# 9.net
KiCad netlist of a schematic drawn in EasyEDA Pro
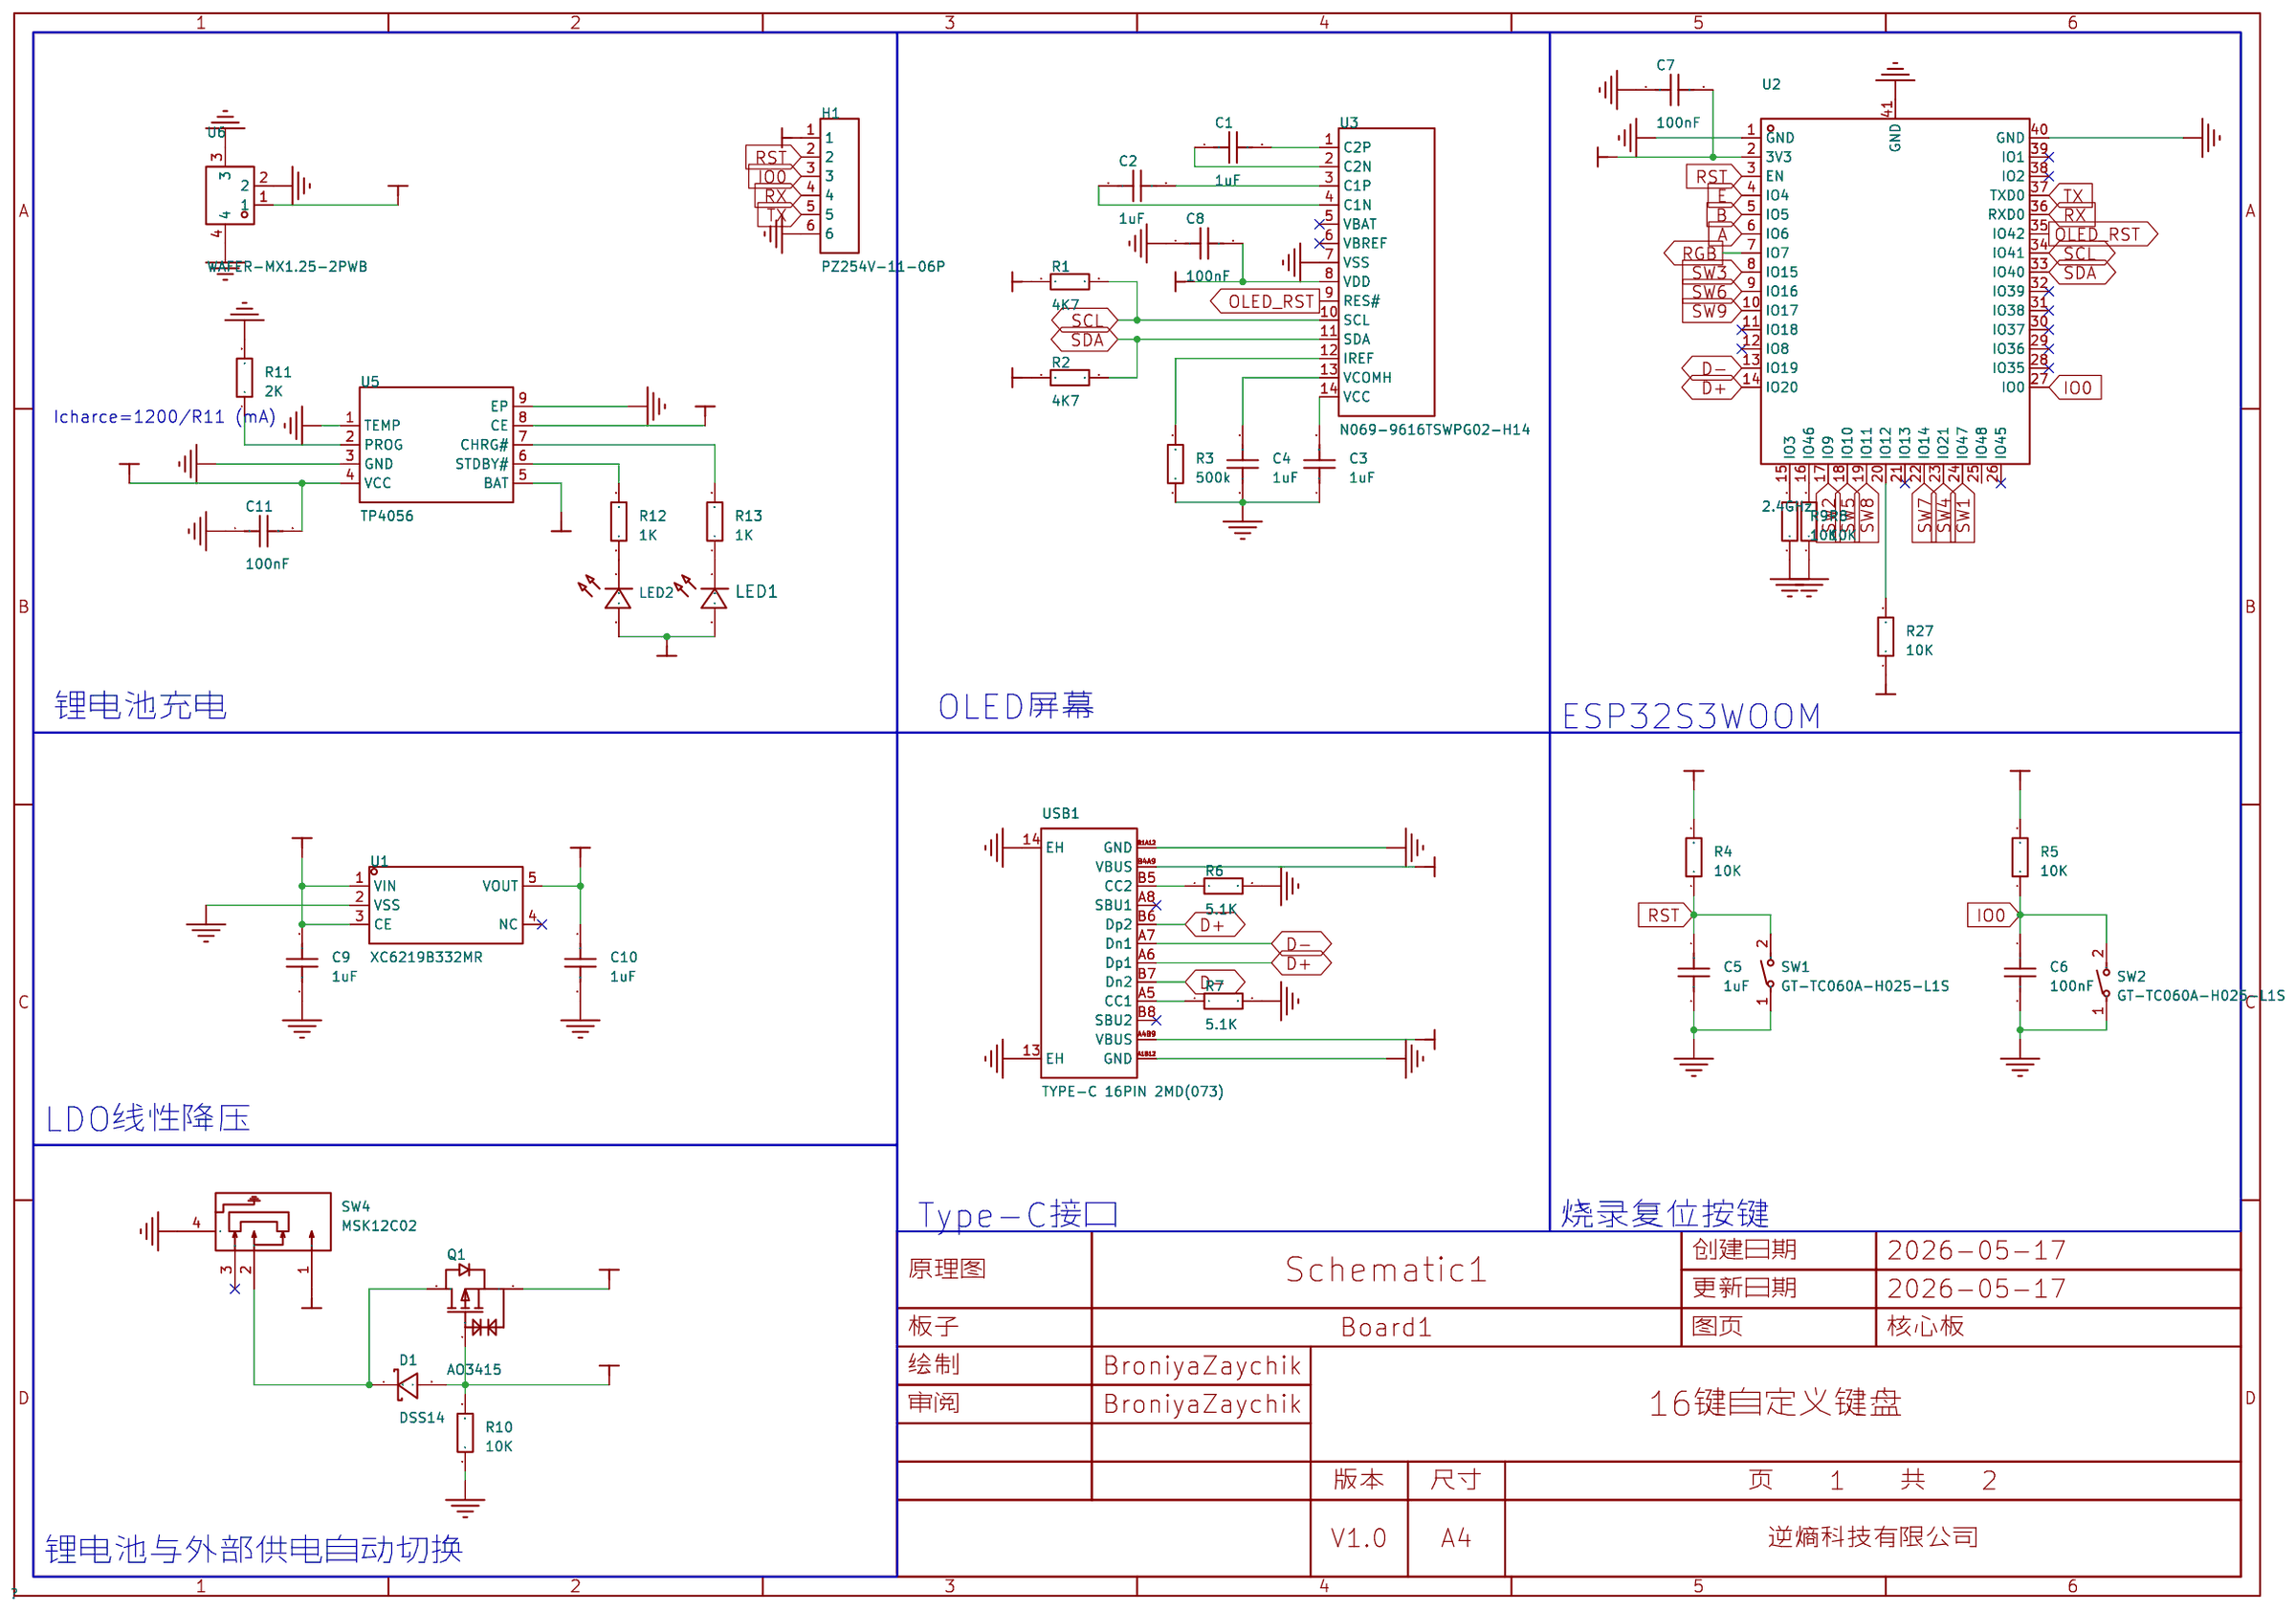
[diagram p0: 核心板]
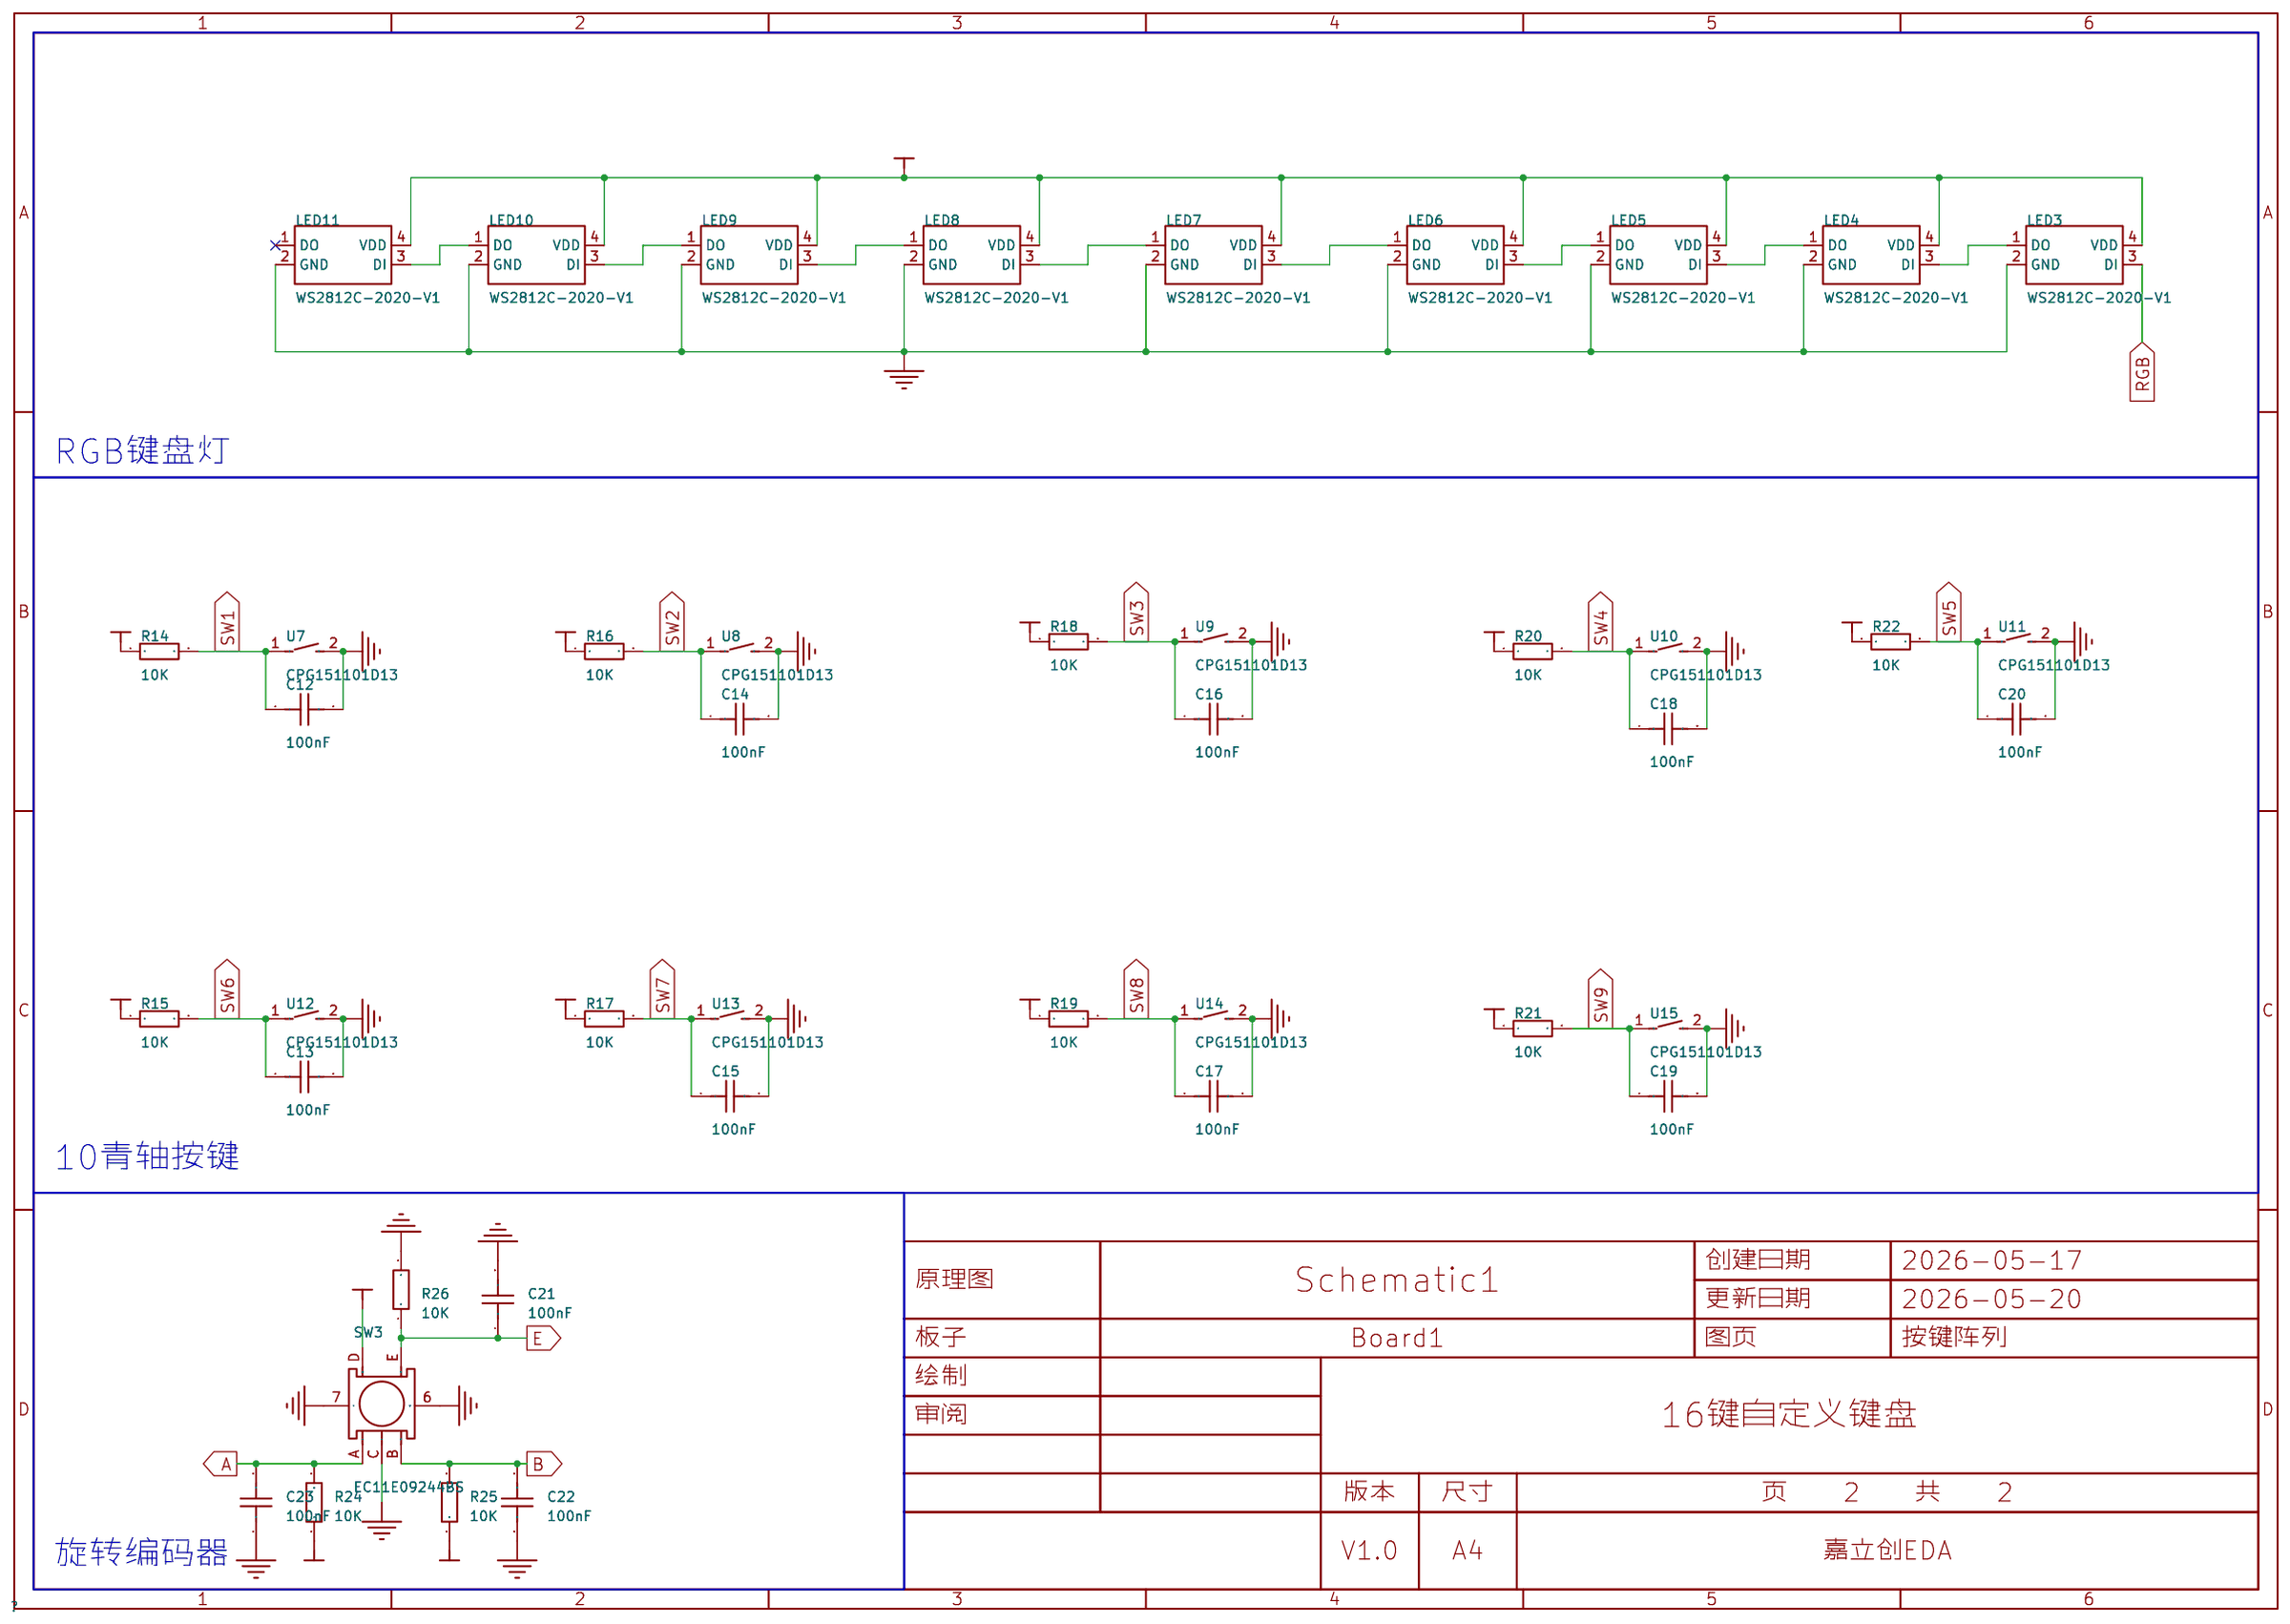
[diagram p1: 按键阵列]

(export (version "E")
  (design (tool "Eeschema 10.0.6"))
  (components
    (comp (ref "C1")
      (value "1uF")
      (footprint "easyedapro:C0603")
      (libsource (lib "easyedapro") (part "Capacitance"))
    )
    (comp (ref "C2")
      (value "1uF")
      (footprint "easyedapro:C0603")
      (libsource (lib "easyedapro") (part "Capacitance"))
    )
    (comp (ref "C3")
      (value "1uF")
      (footprint "easyedapro:C0603")
      (libsource (lib "easyedapro") (part "Capacitance"))
    )
    (comp (ref "C4")
      (value "1uF")
      (footprint "easyedapro:C0603")
      (libsource (lib "easyedapro") (part "Capacitance"))
    )
    (comp (ref "C5")
      (value "1uF")
      (footprint "easyedapro:C0603")
      (libsource (lib "easyedapro") (part "Capacitance"))
    )
    (comp (ref "C6")
      (value "100nF")
      (footprint "easyedapro:C0603")
      (libsource (lib "easyedapro") (part "Capacitance"))
    )
    (comp (ref "C7")
      (value "100nF")
      (footprint "easyedapro:C0603")
      (libsource (lib "easyedapro") (part "Capacitance"))
    )
    (comp (ref "C8")
      (value "100nF")
      (footprint "easyedapro:C0603")
      (libsource (lib "easyedapro") (part "Capacitance"))
    )
    (comp (ref "C9")
      (value "1uF")
      (footprint "easyedapro:C0603")
      (libsource (lib "easyedapro") (part "Capacitance"))
    )
    (comp (ref "C10")
      (value "1uF")
      (footprint "easyedapro:C0603")
      (libsource (lib "easyedapro") (part "Capacitance"))
    )
    (comp (ref "C11")
      (value "100nF")
      (footprint "easyedapro:C0603")
      (libsource (lib "easyedapro") (part "Capacitance"))
    )
    (comp (ref "D1")
      (value "DSS14")
      (footprint "easyedapro:SOD-123FL_L2.8-W1.8-LS3.7-RD")
      (fields (field (name "Manufacturer") "CJ(江苏长电/长晶)"))
      (libsource (lib "easyedapro") (part "DSS14_C2923923"))
    )
    (comp (ref "H1")
      (value "PZ254V-11-06P")
      (footprint "easyedapro:HDR-TH_6P-P2.54-V-M")
      (fields (field (name "Manufacturer") "XFCN(兴飞)"))
      (libsource (lib "easyedapro") (part "PZ254V-11-06P"))
    )
    (comp (ref "LED1")
      (value "~")
      (footprint "easyedapro:LED_0603")
      (libsource (lib "easyedapro") (part "LED_R"))
    )
    (comp (ref "LED2")
      (value "~")
      (footprint "easyedapro:LED_0603")
      (libsource (lib "easyedapro") (part "LED_G"))
    )
    (comp (ref "Q1")
      (value "AO3415")
      (footprint "easyedapro:SOT-23_L2.9-W1.3-P1.90-LS2.4-BR")
      (fields (field (name "Manufacturer") "GOODWORK(固得沃克)"))
      (libsource (lib "easyedapro") (part "AO3415_C2938370"))
    )
    (comp (ref "R1") (value "4K7") (footprint "easyedapro:R0603") (libsource (lib "easyedapro") (part "电阻")))
    (comp (ref "R2") (value "4K7") (footprint "easyedapro:R0603") (libsource (lib "easyedapro") (part "电阻")))
    (comp (ref "R3") (value "500k") (footprint "easyedapro:R0603") (libsource (lib "easyedapro") (part "电阻")))
    (comp (ref "R4") (value "10K") (footprint "easyedapro:R0603") (libsource (lib "easyedapro") (part "电阻")))
    (comp (ref "R5") (value "10K") (footprint "easyedapro:R0603") (libsource (lib "easyedapro") (part "电阻")))
    (comp (ref "R6") (value "5.1K") (footprint "easyedapro:R0603") (libsource (lib "easyedapro") (part "电阻")))
    (comp (ref "R7") (value "5.1K") (footprint "easyedapro:R0603") (libsource (lib "easyedapro") (part "电阻")))
    (comp (ref "R8") (value "10K") (footprint "easyedapro:R0603") (libsource (lib "easyedapro") (part "电阻")))
    (comp (ref "R9") (value "10K") (footprint "easyedapro:R0603") (libsource (lib "easyedapro") (part "电阻")))
    (comp (ref "R10") (value "10K") (footprint "easyedapro:R0603") (libsource (lib "easyedapro") (part "电阻")))
    (comp (ref "R11") (value "2K") (footprint "easyedapro:R0603") (libsource (lib "easyedapro") (part "电阻")))
    (comp (ref "R12") (value "1K") (footprint "easyedapro:R0603") (libsource (lib "easyedapro") (part "电阻")))
    (comp (ref "R13") (value "1K") (footprint "easyedapro:R0603") (libsource (lib "easyedapro") (part "电阻")))
    (comp (ref "R27") (value "10K") (footprint "easyedapro:R0603") (libsource (lib "easyedapro") (part "电阻")))
    (comp (ref "SW1")
      (value "GT-TC060A-H025-L1S")
      (footprint "easyedapro:SW-SMD_L6.1-W3.5-LS8.0")
      (fields (field (name "Manufacturer") "G-Switch(品赞)"))
      (libsource (lib "easyedapro") (part "GT-TC060A-H025-L1S"))
    )
    (comp (ref "SW2")
      (value "GT-TC060A-H025-L1S")
      (footprint "easyedapro:SW-SMD_L6.1-W3.5-LS8.0")
      (fields (field (name "Manufacturer") "G-Switch(品赞)"))
      (libsource (lib "easyedapro") (part "GT-TC060A-H025-L1S"))
    )
    (comp (ref "SW4")
      (value "MSK12C02")
      (footprint "easyedapro:SW-TH_MSK12C02")
      (fields (field (name "Manufacturer") "SHOU HAN(首韩)"))
      (libsource (lib "easyedapro") (part "MSK12C02"))
    )
    (comp (ref "U1")
      (value "XC6219B332MR")
      (footprint "easyedapro:SOT-23-5_L3.0-W1.7-P0.95-LS2.8-BR")
      (fields (field (name "Manufacturer") "UMW(友台半导体)"))
      (libsource (lib "easyedapro") (part "XC6219B332MR_C347386"))
    )
    (comp (ref "U2")
      (value "2.4GHz")
      (footprint "easyedapro:WIRELM-SMD_ESP32-S3-WROOM-1")
      (fields
        (field (name "Manufacturer Part") "ESP32-S3-WROOM-1-N8R8")
        (field (name "Manufacturer") "ESPRESSIF(乐鑫)")
      )
      (libsource (lib "easyedapro") (part "ESP32-S3-WROOM-1(N8R8)"))
    )
    (comp (ref "U3")
      (value "N069-9616TSWPG02-H14")
      (footprint "easyedapro:LCD-SMD_N069-9616TSWPG02-H14")
      (fields (field (name "Manufacturer") "Wisevision(新智景)"))
      (libsource (lib "easyedapro") (part "N069-9616TSWPG02-H14"))
    )
    (comp (ref "U5")
      (value "TP4056")
      (footprint "easyedapro:ESOP-8_L4.9-W3.9-P1.27-LS6.0-BL-EP")
      (fields (field (name "Manufacturer") "UMW(友台半导体)"))
      (libsource (lib "easyedapro") (part "TP4056_C725790"))
    )
    (comp (ref "U6")
      (value "WAFER-MX1.25-2PWB")
      (footprint "easyedapro:CONN-SMD_2P-P1.25_XUNPU_WAFER-MX1.25-2PWB")
      (fields (field (name "Manufacturer") "XUNPU(讯普)"))
      (libsource (lib "easyedapro") (part "WAFER-MX1.25-2PWB"))
    )
    (comp (ref "USB1")
      (value "TYPE-C 16PIN 2MD(073)")
      (footprint "easyedapro:USB-C-SMD_TYPE-C-16PIN-2MD-073")
      (fields (field (name "Manufacturer") "SHOU HAN(首韩)"))
      (libsource (lib "easyedapro") (part "TYPE-C 16PIN 2MD(073)"))
    )
    (comp (ref "C12")
      (value "100nF")
      (footprint "easyedapro:C0603")
      (libsource (lib "easyedapro") (part "Capacitance"))
    )
    (comp (ref "C13")
      (value "100nF")
      (footprint "easyedapro:C0603")
      (libsource (lib "easyedapro") (part "Capacitance"))
    )
    (comp (ref "C14")
      (value "100nF")
      (footprint "easyedapro:C0603")
      (libsource (lib "easyedapro") (part "Capacitance"))
    )
    (comp (ref "C15")
      (value "100nF")
      (footprint "easyedapro:C0603")
      (libsource (lib "easyedapro") (part "Capacitance"))
    )
    (comp (ref "C16")
      (value "100nF")
      (footprint "easyedapro:C0603")
      (libsource (lib "easyedapro") (part "Capacitance"))
    )
    (comp (ref "C17")
      (value "100nF")
      (footprint "easyedapro:C0603")
      (libsource (lib "easyedapro") (part "Capacitance"))
    )
    (comp (ref "C18")
      (value "100nF")
      (footprint "easyedapro:C0603")
      (libsource (lib "easyedapro") (part "Capacitance"))
    )
    (comp (ref "C19")
      (value "100nF")
      (footprint "easyedapro:C0603")
      (libsource (lib "easyedapro") (part "Capacitance"))
    )
    (comp (ref "C20")
      (value "100nF")
      (footprint "easyedapro:C0603")
      (libsource (lib "easyedapro") (part "Capacitance"))
    )
    (comp (ref "C21")
      (value "100nF")
      (footprint "easyedapro:C0603")
      (libsource (lib "easyedapro") (part "Capacitance"))
    )
    (comp (ref "C22")
      (value "100nF")
      (footprint "easyedapro:C0603")
      (libsource (lib "easyedapro") (part "Capacitance"))
    )
    (comp (ref "C23")
      (value "100nF")
      (footprint "easyedapro:C0603")
      (libsource (lib "easyedapro") (part "Capacitance"))
    )
    (comp (ref "LED3")
      (value "WS2812C-2020-V1")
      (footprint "easyedapro:LED-SMD_4P-L2.0-W2.0-TL_WS2812B-2020")
      (fields (field (name "Manufacturer") "worldsemi"))
      (libsource (lib "easyedapro") (part "WS2812C-2020-V1"))
    )
    (comp (ref "LED4")
      (value "WS2812C-2020-V1")
      (footprint "easyedapro:LED-SMD_4P-L2.0-W2.0-TL_WS2812B-2020")
      (fields (field (name "Manufacturer") "worldsemi"))
      (libsource (lib "easyedapro") (part "WS2812C-2020-V1"))
    )
    (comp (ref "LED5")
      (value "WS2812C-2020-V1")
      (footprint "easyedapro:LED-SMD_4P-L2.0-W2.0-TL_WS2812B-2020")
      (fields (field (name "Manufacturer") "worldsemi"))
      (libsource (lib "easyedapro") (part "WS2812C-2020-V1"))
    )
    (comp (ref "LED6")
      (value "WS2812C-2020-V1")
      (footprint "easyedapro:LED-SMD_4P-L2.0-W2.0-TL_WS2812B-2020")
      (fields (field (name "Manufacturer") "worldsemi"))
      (libsource (lib "easyedapro") (part "WS2812C-2020-V1"))
    )
    (comp (ref "LED7")
      (value "WS2812C-2020-V1")
      (footprint "easyedapro:LED-SMD_4P-L2.0-W2.0-TL_WS2812B-2020")
      (fields (field (name "Manufacturer") "worldsemi"))
      (libsource (lib "easyedapro") (part "WS2812C-2020-V1"))
    )
    (comp (ref "LED8")
      (value "WS2812C-2020-V1")
      (footprint "easyedapro:LED-SMD_4P-L2.0-W2.0-TL_WS2812B-2020")
      (fields (field (name "Manufacturer") "worldsemi"))
      (libsource (lib "easyedapro") (part "WS2812C-2020-V1"))
    )
    (comp (ref "LED9")
      (value "WS2812C-2020-V1")
      (footprint "easyedapro:LED-SMD_4P-L2.0-W2.0-TL_WS2812B-2020")
      (fields (field (name "Manufacturer") "worldsemi"))
      (libsource (lib "easyedapro") (part "WS2812C-2020-V1"))
    )
    (comp (ref "LED10")
      (value "WS2812C-2020-V1")
      (footprint "easyedapro:LED-SMD_4P-L2.0-W2.0-TL_WS2812B-2020")
      (fields (field (name "Manufacturer") "worldsemi"))
      (libsource (lib "easyedapro") (part "WS2812C-2020-V1"))
    )
    (comp (ref "LED11")
      (value "WS2812C-2020-V1")
      (footprint "easyedapro:LED-SMD_4P-L2.0-W2.0-TL_WS2812B-2020")
      (fields (field (name "Manufacturer") "worldsemi"))
      (libsource (lib "easyedapro") (part "WS2812C-2020-V1"))
    )
    (comp (ref "R14") (value "10K") (footprint "easyedapro:R0603") (libsource (lib "easyedapro") (part "电阻")))
    (comp (ref "R15") (value "10K") (footprint "easyedapro:R0603") (libsource (lib "easyedapro") (part "电阻")))
    (comp (ref "R16") (value "10K") (footprint "easyedapro:R0603") (libsource (lib "easyedapro") (part "电阻")))
    (comp (ref "R17") (value "10K") (footprint "easyedapro:R0603") (libsource (lib "easyedapro") (part "电阻")))
    (comp (ref "R18") (value "10K") (footprint "easyedapro:R0603") (libsource (lib "easyedapro") (part "电阻")))
    (comp (ref "R19") (value "10K") (footprint "easyedapro:R0603") (libsource (lib "easyedapro") (part "电阻")))
    (comp (ref "R20") (value "10K") (footprint "easyedapro:R0603") (libsource (lib "easyedapro") (part "电阻")))
    (comp (ref "R21") (value "10K") (footprint "easyedapro:R0603") (libsource (lib "easyedapro") (part "电阻")))
    (comp (ref "R22") (value "10K") (footprint "easyedapro:R0603") (libsource (lib "easyedapro") (part "电阻")))
    (comp (ref "R24") (value "10K") (footprint "easyedapro:R0603") (libsource (lib "easyedapro") (part "电阻")))
    (comp (ref "R25") (value "10K") (footprint "easyedapro:R0603") (libsource (lib "easyedapro") (part "电阻")))
    (comp (ref "R26") (value "10K") (footprint "easyedapro:R0603") (libsource (lib "easyedapro") (part "电阻")))
    (comp (ref "SW3")
      (value "EC11E09244BS")
      (footprint "easyedapro:SW-TH_EC11XXXXXXXX")
      (fields (field (name "Manufacturer") "ALPSALPINE(阿尔卑斯阿尔派)"))
      (libsource (lib "easyedapro") (part "EC11E09244BS"))
    )
    (comp (ref "U7")
      (value "CPG151101D13")
      (footprint "easyedapro:KEY-TH_CPG151101D21X")
      (fields (field (name "Manufacturer") "HanElectricity(瀚源)"))
      (libsource (lib "easyedapro") (part "CPG151101D13"))
    )
    (comp (ref "U8")
      (value "CPG151101D13")
      (footprint "easyedapro:KEY-TH_CPG151101D21X")
      (fields (field (name "Manufacturer") "HanElectricity(瀚源)"))
      (libsource (lib "easyedapro") (part "CPG151101D13"))
    )
    (comp (ref "U9")
      (value "CPG151101D13")
      (footprint "easyedapro:KEY-TH_CPG151101D21X")
      (fields (field (name "Manufacturer") "HanElectricity(瀚源)"))
      (libsource (lib "easyedapro") (part "CPG151101D13"))
    )
    (comp (ref "U10")
      (value "CPG151101D13")
      (footprint "easyedapro:KEY-TH_CPG151101D21X")
      (fields (field (name "Manufacturer") "HanElectricity(瀚源)"))
      (libsource (lib "easyedapro") (part "CPG151101D13"))
    )
    (comp (ref "U11")
      (value "CPG151101D13")
      (footprint "easyedapro:KEY-TH_CPG151101D21X")
      (fields (field (name "Manufacturer") "HanElectricity(瀚源)"))
      (libsource (lib "easyedapro") (part "CPG151101D13"))
    )
    (comp (ref "U12")
      (value "CPG151101D13")
      (footprint "easyedapro:KEY-TH_CPG151101D21X")
      (fields (field (name "Manufacturer") "HanElectricity(瀚源)"))
      (libsource (lib "easyedapro") (part "CPG151101D13"))
    )
    (comp (ref "U13")
      (value "CPG151101D13")
      (footprint "easyedapro:KEY-TH_CPG151101D21X")
      (fields (field (name "Manufacturer") "HanElectricity(瀚源)"))
      (libsource (lib "easyedapro") (part "CPG151101D13"))
    )
    (comp (ref "U14")
      (value "CPG151101D13")
      (footprint "easyedapro:KEY-TH_CPG151101D21X")
      (fields (field (name "Manufacturer") "HanElectricity(瀚源)"))
      (libsource (lib "easyedapro") (part "CPG151101D13"))
    )
    (comp (ref "U15")
      (value "CPG151101D13")
      (footprint "easyedapro:KEY-TH_CPG151101D21X")
      (fields (field (name "Manufacturer") "HanElectricity(瀚源)"))
      (libsource (lib "easyedapro") (part "CPG151101D13"))
    )
  )
  (nets
    (net (code "1") (name "+5V") (class "Default")
      (node (ref "C11") (pin "2") (pinfunction "2_2") (pintype "input"))
      (node (ref "D1") (pin "2") (pinfunction "A_2") (pintype "unspecified"))
      (node (ref "LED1") (pin "2") (pinfunction "A_2") (pintype "input"))
      (node (ref "LED2") (pin "2") (pinfunction "A_2") (pintype "input"))
      (node (ref "Q1") (pin "1") (pinfunction "G_1") (pintype "unspecified"))
      (node (ref "R10") (pin "2") (pinfunction "2_2") (pintype "input"))
      (node (ref "R27") (pin "1") (pinfunction "1_1") (pintype "input"))
      (node (ref "U5") (pin "4") (pinfunction "VCC_4") (pintype "unspecified"))
      (node (ref "U5") (pin "8") (pinfunction "CE_8") (pintype "unspecified"))
      (node (ref "USB1") (pin "A4B9") (pinfunction "VBUS_A4B9") (pintype "unspecified"))
      (node (ref "USB1") (pin "B4A9") (pinfunction "VBUS_B4A9") (pintype "unspecified"))
    )
    (net (code "2") (name "3V3") (class "Default")
      (node (ref "C10") (pin "1") (pinfunction "1_1") (pintype "input"))
      (node (ref "C7") (pin "2") (pinfunction "2_2") (pintype "input"))
      (node (ref "C8") (pin "2") (pinfunction "2_2") (pintype "input"))
      (node (ref "H1") (pin "1") (pinfunction "1_1") (pintype "unspecified"))
      (node (ref "R1") (pin "1") (pinfunction "1_1") (pintype "input"))
      (node (ref "R14") (pin "1") (pinfunction "1_1") (pintype "input"))
      (node (ref "R15") (pin "1") (pinfunction "1_1") (pintype "input"))
      (node (ref "R16") (pin "1") (pinfunction "1_1") (pintype "input"))
      (node (ref "R17") (pin "1") (pinfunction "1_1") (pintype "input"))
      (node (ref "R18") (pin "1") (pinfunction "1_1") (pintype "input"))
      (node (ref "R19") (pin "1") (pinfunction "1_1") (pintype "input"))
      (node (ref "R2") (pin "1") (pinfunction "1_1") (pintype "input"))
      (node (ref "R20") (pin "1") (pinfunction "1_1") (pintype "input"))
      (node (ref "R21") (pin "1") (pinfunction "1_1") (pintype "input"))
      (node (ref "R22") (pin "1") (pinfunction "1_1") (pintype "input"))
      (node (ref "R24") (pin "1") (pinfunction "1_1") (pintype "input"))
      (node (ref "R25") (pin "1") (pinfunction "1_1") (pintype "input"))
      (node (ref "R4") (pin "2") (pinfunction "2_2") (pintype "input"))
      (node (ref "R5") (pin "2") (pinfunction "2_2") (pintype "input"))
      (node (ref "SW3") (pin "D") (pinfunction "D_D") (pintype "unspecified"))
      (node (ref "U1") (pin "5") (pinfunction "VOUT_5") (pintype "unspecified"))
      (node (ref "U2") (pin "2") (pinfunction "3V3_2") (pintype "unspecified"))
      (node (ref "U3") (pin "8") (pinfunction "VDD_8") (pintype "unspecified"))
    )
    (net (code "3") (name "A") (class "Default")
      (node (ref "C23") (pin "2") (pinfunction "2_2") (pintype "input"))
      (node (ref "R24") (pin "2") (pinfunction "2_2") (pintype "input"))
      (node (ref "SW3") (pin "A") (pinfunction "A_A") (pintype "unspecified"))
      (node (ref "U2") (pin "6") (pinfunction "IO6_6") (pintype "unspecified"))
    )
    (net (code "4") (name "B") (class "Default")
      (node (ref "C22") (pin "2") (pinfunction "2_2") (pintype "input"))
      (node (ref "R25") (pin "2") (pinfunction "2_2") (pintype "input"))
      (node (ref "SW3") (pin "B") (pinfunction "B_B") (pintype "unspecified"))
      (node (ref "U2") (pin "5") (pinfunction "IO5_5") (pintype "unspecified"))
    )
    (net (code "5") (name "D+") (class "Default")
      (node (ref "U2") (pin "14") (pinfunction "IO20_14") (pintype "unspecified"))
      (node (ref "USB1") (pin "A6") (pinfunction "Dp1_A6") (pintype "unspecified"))
      (node (ref "USB1") (pin "B6") (pinfunction "Dp2_B6") (pintype "unspecified"))
    )
    (net (code "6") (name "D-") (class "Default")
      (node (ref "U2") (pin "13") (pinfunction "IO19_13") (pintype "unspecified"))
      (node (ref "USB1") (pin "A7") (pinfunction "Dn1_A7") (pintype "unspecified"))
      (node (ref "USB1") (pin "B7") (pinfunction "Dn2_B7") (pintype "unspecified"))
    )
    (net (code "7") (name "E") (class "Default")
      (node (ref "C21") (pin "1") (pinfunction "1_1") (pintype "input"))
      (node (ref "R26") (pin "1") (pinfunction "1_1") (pintype "input"))
      (node (ref "SW3") (pin "E") (pinfunction "E_E") (pintype "unspecified"))
      (node (ref "U2") (pin "4") (pinfunction "IO4_4") (pintype "unspecified"))
    )
    (net (code "8") (name "GND") (class "Default")
      (node (ref "C10") (pin "2") (pinfunction "2_2") (pintype "input"))
      (node (ref "C11") (pin "1") (pinfunction "1_1") (pintype "input"))
      (node (ref "C12") (pin "2") (pinfunction "2_2") (pintype "input"))
      (node (ref "C13") (pin "2") (pinfunction "2_2") (pintype "input"))
      (node (ref "C14") (pin "2") (pinfunction "2_2") (pintype "input"))
      (node (ref "C15") (pin "2") (pinfunction "2_2") (pintype "input"))
      (node (ref "C16") (pin "2") (pinfunction "2_2") (pintype "input"))
      (node (ref "C17") (pin "2") (pinfunction "2_2") (pintype "input"))
      (node (ref "C18") (pin "2") (pinfunction "2_2") (pintype "input"))
      (node (ref "C19") (pin "2") (pinfunction "2_2") (pintype "input"))
      (node (ref "C20") (pin "2") (pinfunction "2_2") (pintype "input"))
      (node (ref "C21") (pin "2") (pinfunction "2_2") (pintype "input"))
      (node (ref "C22") (pin "1") (pinfunction "1_1") (pintype "input"))
      (node (ref "C23") (pin "1") (pinfunction "1_1") (pintype "input"))
      (node (ref "C3") (pin "1") (pinfunction "1_1") (pintype "input"))
      (node (ref "C4") (pin "1") (pinfunction "1_1") (pintype "input"))
      (node (ref "C5") (pin "2") (pinfunction "2_2") (pintype "input"))
      (node (ref "C6") (pin "2") (pinfunction "2_2") (pintype "input"))
      (node (ref "C7") (pin "1") (pinfunction "1_1") (pintype "input"))
      (node (ref "C8") (pin "1") (pinfunction "1_1") (pintype "input"))
      (node (ref "C9") (pin "1") (pinfunction "1_1") (pintype "input"))
      (node (ref "H1") (pin "6") (pinfunction "6_6") (pintype "unspecified"))
      (node (ref "LED10") (pin "2") (pinfunction "GND_2") (pintype "unspecified"))
      (node (ref "LED11") (pin "2") (pinfunction "GND_2") (pintype "unspecified"))
      (node (ref "LED3") (pin "2") (pinfunction "GND_2") (pintype "unspecified"))
      (node (ref "LED4") (pin "2") (pinfunction "GND_2") (pintype "unspecified"))
      (node (ref "LED5") (pin "2") (pinfunction "GND_2") (pintype "unspecified"))
      (node (ref "LED6") (pin "2") (pinfunction "GND_2") (pintype "unspecified"))
      (node (ref "LED7") (pin "2") (pinfunction "GND_2") (pintype "unspecified"))
      (node (ref "LED8") (pin "2") (pinfunction "GND_2") (pintype "unspecified"))
      (node (ref "LED9") (pin "2") (pinfunction "GND_2") (pintype "unspecified"))
      (node (ref "R10") (pin "1") (pinfunction "1_1") (pintype "input"))
      (node (ref "R11") (pin "2") (pinfunction "2_2") (pintype "input"))
      (node (ref "R26") (pin "2") (pinfunction "2_2") (pintype "input"))
      (node (ref "R3") (pin "1") (pinfunction "1_1") (pintype "input"))
      (node (ref "R6") (pin "2") (pinfunction "2_2") (pintype "input"))
      (node (ref "R7") (pin "2") (pinfunction "2_2") (pintype "input"))
      (node (ref "R8") (pin "1") (pinfunction "1_1") (pintype "input"))
      (node (ref "R9") (pin "1") (pinfunction "1_1") (pintype "input"))
      (node (ref "SW1") (pin "1") (pinfunction "1_1") (pintype "unspecified"))
      (node (ref "SW2") (pin "1") (pinfunction "1_1") (pintype "unspecified"))
      (node (ref "SW3") (pin "6") (pinfunction "6_6") (pintype "unspecified"))
      (node (ref "SW3") (pin "7") (pinfunction "7_7") (pintype "unspecified"))
      (node (ref "SW3") (pin "C") (pinfunction "C_C") (pintype "unspecified"))
      (node (ref "SW4") (pin "4") (pinfunction "4_4") (pintype "unspecified"))
      (node (ref "U1") (pin "2") (pinfunction "VSS_2") (pintype "unspecified"))
      (node (ref "U10") (pin "2") (pinfunction "2_2") (pintype "unspecified"))
      (node (ref "U11") (pin "2") (pinfunction "2_2") (pintype "unspecified"))
      (node (ref "U12") (pin "2") (pinfunction "2_2") (pintype "unspecified"))
      (node (ref "U13") (pin "2") (pinfunction "2_2") (pintype "unspecified"))
      (node (ref "U14") (pin "2") (pinfunction "2_2") (pintype "unspecified"))
      (node (ref "U15") (pin "2") (pinfunction "2_2") (pintype "unspecified"))
      (node (ref "U2") (pin "1") (pinfunction "GND_1") (pintype "unspecified"))
      (node (ref "U2") (pin "40") (pinfunction "GND_40") (pintype "unspecified"))
      (node (ref "U2") (pin "41") (pinfunction "GND_41") (pintype "unspecified"))
      (node (ref "U3") (pin "7") (pinfunction "VSS_7") (pintype "unspecified"))
      (node (ref "U5") (pin "1") (pinfunction "TEMP_1") (pintype "unspecified"))
      (node (ref "U5") (pin "3") (pinfunction "GND_3") (pintype "unspecified"))
      (node (ref "U5") (pin "9") (pinfunction "EP_9") (pintype "unspecified"))
      (node (ref "U6") (pin "2") (pinfunction "2_2") (pintype "unspecified"))
      (node (ref "U6") (pin "3") (pinfunction "3_3") (pintype "unspecified"))
      (node (ref "U6") (pin "4") (pinfunction "4_4") (pintype "unspecified"))
      (node (ref "U7") (pin "2") (pinfunction "2_2") (pintype "unspecified"))
      (node (ref "U8") (pin "2") (pinfunction "2_2") (pintype "unspecified"))
      (node (ref "U9") (pin "2") (pinfunction "2_2") (pintype "unspecified"))
      (node (ref "USB1") (pin "13") (pinfunction "EH_13") (pintype "unspecified"))
      (node (ref "USB1") (pin "14") (pinfunction "EH_14") (pintype "unspecified"))
      (node (ref "USB1") (pin "A1B12") (pinfunction "GND_A1B12") (pintype "unspecified"))
      (node (ref "USB1") (pin "B1A12") (pinfunction "GND_B1A12") (pintype "unspecified"))
    )
    (net (code "9") (name "IO0") (class "Default")
      (node (ref "C6") (pin "1") (pinfunction "1_1") (pintype "input"))
      (node (ref "H1") (pin "3") (pinfunction "3_3") (pintype "unspecified"))
      (node (ref "R5") (pin "1") (pinfunction "1_1") (pintype "input"))
      (node (ref "SW2") (pin "2") (pinfunction "2_2") (pintype "unspecified"))
      (node (ref "U2") (pin "27") (pinfunction "IO0_27") (pintype "unspecified"))
    )
    (net (code "10") (name "Net-(D1-C)") (class "Default")
      (node (ref "D1") (pin "1") (pinfunction "C_1") (pintype "unspecified"))
      (node (ref "Q1") (pin "3") (pinfunction "D_3") (pintype "unspecified"))
      (node (ref "SW4") (pin "2") (pinfunction "2_2") (pintype "unspecified"))
    )
    (net (code "11") (name "Net-(LED1-C)") (class "Default")
      (node (ref "LED1") (pin "1") (pinfunction "C_1") (pintype "input"))
      (node (ref "R13") (pin "1") (pinfunction "1_1") (pintype "input"))
    )
    (net (code "12") (name "Net-(LED2-C)") (class "Default")
      (node (ref "LED2") (pin "1") (pinfunction "C_1") (pintype "input"))
      (node (ref "R12") (pin "1") (pinfunction "1_1") (pintype "input"))
    )
    (net (code "13") (name "Net-(LED3-DO)") (class "Default")
      (node (ref "LED3") (pin "1") (pinfunction "DO_1") (pintype "unspecified"))
      (node (ref "LED4") (pin "3") (pinfunction "DI_3") (pintype "unspecified"))
    )
    (net (code "14") (name "Net-(LED4-DO)") (class "Default")
      (node (ref "LED4") (pin "1") (pinfunction "DO_1") (pintype "unspecified"))
      (node (ref "LED5") (pin "3") (pinfunction "DI_3") (pintype "unspecified"))
    )
    (net (code "15") (name "Net-(LED5-DO)") (class "Default")
      (node (ref "LED5") (pin "1") (pinfunction "DO_1") (pintype "unspecified"))
      (node (ref "LED6") (pin "3") (pinfunction "DI_3") (pintype "unspecified"))
    )
    (net (code "16") (name "Net-(LED6-DO)") (class "Default")
      (node (ref "LED6") (pin "1") (pinfunction "DO_1") (pintype "unspecified"))
      (node (ref "LED7") (pin "3") (pinfunction "DI_3") (pintype "unspecified"))
    )
    (net (code "17") (name "Net-(LED7-DO)") (class "Default")
      (node (ref "LED7") (pin "1") (pinfunction "DO_1") (pintype "unspecified"))
      (node (ref "LED8") (pin "3") (pinfunction "DI_3") (pintype "unspecified"))
    )
    (net (code "18") (name "Net-(LED8-DO)") (class "Default")
      (node (ref "LED8") (pin "1") (pinfunction "DO_1") (pintype "unspecified"))
      (node (ref "LED9") (pin "3") (pinfunction "DI_3") (pintype "unspecified"))
    )
    (net (code "19") (name "Net-(LED10-DI)") (class "Default")
      (node (ref "LED10") (pin "3") (pinfunction "DI_3") (pintype "unspecified"))
      (node (ref "LED9") (pin "1") (pinfunction "DO_1") (pintype "unspecified"))
    )
    (net (code "20") (name "Net-(LED10-DO)") (class "Default")
      (node (ref "LED10") (pin "1") (pinfunction "DO_1") (pintype "unspecified"))
      (node (ref "LED11") (pin "3") (pinfunction "DI_3") (pintype "unspecified"))
    )
    (net (code "21") (name "Net-(U2-IO3)") (class "Default")
      (node (ref "R9") (pin "2") (pinfunction "2_2") (pintype "input"))
      (node (ref "U2") (pin "15") (pinfunction "IO3_15") (pintype "unspecified"))
    )
    (net (code "22") (name "Net-(U2-IO12)") (class "Default")
      (node (ref "R27") (pin "2") (pinfunction "2_2") (pintype "input"))
      (node (ref "U2") (pin "20") (pinfunction "IO12_20") (pintype "unspecified"))
    )
    (net (code "23") (name "Net-(U2-IO46)") (class "Default")
      (node (ref "R8") (pin "2") (pinfunction "2_2") (pintype "input"))
      (node (ref "U2") (pin "16") (pinfunction "IO46_16") (pintype "unspecified"))
    )
    (net (code "24") (name "Net-(U3-C1N)") (class "Default")
      (node (ref "C2") (pin "1") (pinfunction "1_1") (pintype "input"))
      (node (ref "U3") (pin "4") (pinfunction "C1N_4") (pintype "unspecified"))
    )
    (net (code "25") (name "Net-(U3-C1P)") (class "Default")
      (node (ref "C2") (pin "2") (pinfunction "2_2") (pintype "input"))
      (node (ref "U3") (pin "3") (pinfunction "C1P_3") (pintype "unspecified"))
    )
    (net (code "26") (name "Net-(U3-C2N)") (class "Default")
      (node (ref "C1") (pin "1") (pinfunction "1_1") (pintype "input"))
      (node (ref "U3") (pin "2") (pinfunction "C2N_2") (pintype "unspecified"))
    )
    (net (code "27") (name "Net-(U3-C2P)") (class "Default")
      (node (ref "C1") (pin "2") (pinfunction "2_2") (pintype "input"))
      (node (ref "U3") (pin "1") (pinfunction "C2P_1") (pintype "unspecified"))
    )
    (net (code "28") (name "Net-(U3-IREF)") (class "Default")
      (node (ref "R3") (pin "2") (pinfunction "2_2") (pintype "input"))
      (node (ref "U3") (pin "12") (pinfunction "IREF_12") (pintype "unspecified"))
    )
    (net (code "29") (name "Net-(U3-VCC)") (class "Default")
      (node (ref "C3") (pin "2") (pinfunction "2_2") (pintype "input"))
      (node (ref "U3") (pin "14") (pinfunction "VCC_14") (pintype "unspecified"))
    )
    (net (code "30") (name "Net-(U3-VCOMH)") (class "Default")
      (node (ref "C4") (pin "2") (pinfunction "2_2") (pintype "input"))
      (node (ref "U3") (pin "13") (pinfunction "VCOMH_13") (pintype "unspecified"))
    )
    (net (code "31") (name "Net-(U5-CHRG#)") (class "Default")
      (node (ref "R13") (pin "2") (pinfunction "2_2") (pintype "input"))
      (node (ref "U5") (pin "7") (pinfunction "CHRG#_7") (pintype "unspecified"))
    )
    (net (code "32") (name "Net-(U5-PROG)") (class "Default")
      (node (ref "R11") (pin "1") (pinfunction "1_1") (pintype "input"))
      (node (ref "U5") (pin "2") (pinfunction "PROG_2") (pintype "unspecified"))
    )
    (net (code "33") (name "Net-(U5-STDBY#)") (class "Default")
      (node (ref "R12") (pin "2") (pinfunction "2_2") (pintype "input"))
      (node (ref "U5") (pin "6") (pinfunction "STDBY#_6") (pintype "unspecified"))
    )
    (net (code "34") (name "Net-(USB1-CC1)") (class "Default")
      (node (ref "R7") (pin "1") (pinfunction "1_1") (pintype "input"))
      (node (ref "USB1") (pin "A5") (pinfunction "CC1_A5") (pintype "unspecified"))
    )
    (net (code "35") (name "Net-(USB1-CC2)") (class "Default")
      (node (ref "R6") (pin "1") (pinfunction "1_1") (pintype "input"))
      (node (ref "USB1") (pin "B5") (pinfunction "CC2_B5") (pintype "unspecified"))
    )
    (net (code "36") (name "OLED_RST") (class "Default")
      (node (ref "U2") (pin "35") (pinfunction "IO42_35") (pintype "unspecified"))
      (node (ref "U3") (pin "9") (pinfunction "RES#_9") (pintype "unspecified"))
    )
    (net (code "37") (name "RGB") (class "Default")
      (node (ref "LED3") (pin "3") (pinfunction "DI_3") (pintype "unspecified"))
      (node (ref "U2") (pin "7") (pinfunction "IO7_7") (pintype "unspecified"))
    )
    (net (code "38") (name "RST") (class "Default")
      (node (ref "C5") (pin "1") (pinfunction "1_1") (pintype "input"))
      (node (ref "H1") (pin "2") (pinfunction "2_2") (pintype "unspecified"))
      (node (ref "R4") (pin "1") (pinfunction "1_1") (pintype "input"))
      (node (ref "SW1") (pin "2") (pinfunction "2_2") (pintype "unspecified"))
      (node (ref "U2") (pin "3") (pinfunction "EN_3") (pintype "unspecified"))
    )
    (net (code "39") (name "RX") (class "Default")
      (node (ref "H1") (pin "4") (pinfunction "4_4") (pintype "unspecified"))
      (node (ref "U2") (pin "36") (pinfunction "RXD0_36") (pintype "unspecified"))
    )
    (net (code "40") (name "SCL") (class "Default")
      (node (ref "R1") (pin "2") (pinfunction "2_2") (pintype "input"))
      (node (ref "U2") (pin "34") (pinfunction "IO41_34") (pintype "unspecified"))
      (node (ref "U3") (pin "10") (pinfunction "SCL_10") (pintype "unspecified"))
    )
    (net (code "41") (name "SDA") (class "Default")
      (node (ref "R2") (pin "2") (pinfunction "2_2") (pintype "input"))
      (node (ref "U2") (pin "33") (pinfunction "IO40_33") (pintype "unspecified"))
      (node (ref "U3") (pin "11") (pinfunction "SDA_11") (pintype "unspecified"))
    )
    (net (code "42") (name "SW1") (class "Default")
      (node (ref "C12") (pin "1") (pinfunction "1_1") (pintype "input"))
      (node (ref "R14") (pin "2") (pinfunction "2_2") (pintype "input"))
      (node (ref "U2") (pin "24") (pinfunction "IO47_24") (pintype "unspecified"))
      (node (ref "U7") (pin "1") (pinfunction "1_1") (pintype "unspecified"))
    )
    (net (code "43") (name "SW2") (class "Default")
      (node (ref "C14") (pin "1") (pinfunction "1_1") (pintype "input"))
      (node (ref "R16") (pin "2") (pinfunction "2_2") (pintype "input"))
      (node (ref "U2") (pin "17") (pinfunction "IO9_17") (pintype "unspecified"))
      (node (ref "U8") (pin "1") (pinfunction "1_1") (pintype "unspecified"))
    )
    (net (code "44") (name "SW3") (class "Default")
      (node (ref "C16") (pin "1") (pinfunction "1_1") (pintype "input"))
      (node (ref "R18") (pin "2") (pinfunction "2_2") (pintype "input"))
      (node (ref "U2") (pin "8") (pinfunction "IO15_8") (pintype "unspecified"))
      (node (ref "U9") (pin "1") (pinfunction "1_1") (pintype "unspecified"))
    )
    (net (code "45") (name "SW4") (class "Default")
      (node (ref "C18") (pin "1") (pinfunction "1_1") (pintype "input"))
      (node (ref "R20") (pin "2") (pinfunction "2_2") (pintype "input"))
      (node (ref "U10") (pin "1") (pinfunction "1_1") (pintype "unspecified"))
      (node (ref "U2") (pin "23") (pinfunction "IO21_23") (pintype "unspecified"))
    )
    (net (code "46") (name "SW5") (class "Default")
      (node (ref "C20") (pin "1") (pinfunction "1_1") (pintype "input"))
      (node (ref "R22") (pin "2") (pinfunction "2_2") (pintype "input"))
      (node (ref "U11") (pin "1") (pinfunction "1_1") (pintype "unspecified"))
      (node (ref "U2") (pin "18") (pinfunction "IO10_18") (pintype "unspecified"))
    )
    (net (code "47") (name "SW6") (class "Default")
      (node (ref "C13") (pin "1") (pinfunction "1_1") (pintype "input"))
      (node (ref "R15") (pin "2") (pinfunction "2_2") (pintype "input"))
      (node (ref "U12") (pin "1") (pinfunction "1_1") (pintype "unspecified"))
      (node (ref "U2") (pin "9") (pinfunction "IO16_9") (pintype "unspecified"))
    )
    (net (code "48") (name "SW7") (class "Default")
      (node (ref "C15") (pin "1") (pinfunction "1_1") (pintype "input"))
      (node (ref "R17") (pin "2") (pinfunction "2_2") (pintype "input"))
      (node (ref "U13") (pin "1") (pinfunction "1_1") (pintype "unspecified"))
      (node (ref "U2") (pin "22") (pinfunction "IO14_22") (pintype "unspecified"))
    )
    (net (code "49") (name "SW8") (class "Default")
      (node (ref "C17") (pin "1") (pinfunction "1_1") (pintype "input"))
      (node (ref "R19") (pin "2") (pinfunction "2_2") (pintype "input"))
      (node (ref "U14") (pin "1") (pinfunction "1_1") (pintype "unspecified"))
      (node (ref "U2") (pin "19") (pinfunction "IO11_19") (pintype "unspecified"))
    )
    (net (code "50") (name "SW9") (class "Default")
      (node (ref "C19") (pin "1") (pinfunction "1_1") (pintype "input"))
      (node (ref "R21") (pin "2") (pinfunction "2_2") (pintype "input"))
      (node (ref "U15") (pin "1") (pinfunction "1_1") (pintype "unspecified"))
      (node (ref "U2") (pin "10") (pinfunction "IO17_10") (pintype "unspecified"))
    )
    (net (code "51") (name "TX") (class "Default")
      (node (ref "H1") (pin "5") (pinfunction "5_5") (pintype "unspecified"))
      (node (ref "U2") (pin "37") (pinfunction "TXD0_37") (pintype "unspecified"))
    )
    (net (code "52") (name "VBAT") (class "Default")
      (node (ref "Q1") (pin "2") (pinfunction "S_2") (pintype "unspecified"))
      (node (ref "U5") (pin "5") (pinfunction "BAT_5") (pintype "unspecified"))
      (node (ref "U6") (pin "1") (pinfunction "1_1") (pintype "unspecified"))
    )
    (net (code "53") (name "VCC") (class "Default")
      (node (ref "C9") (pin "2") (pinfunction "2_2") (pintype "input"))
      (node (ref "LED10") (pin "4") (pinfunction "VDD_4") (pintype "unspecified"))
      (node (ref "LED11") (pin "4") (pinfunction "VDD_4") (pintype "unspecified"))
      (node (ref "LED3") (pin "4") (pinfunction "VDD_4") (pintype "unspecified"))
      (node (ref "LED4") (pin "4") (pinfunction "VDD_4") (pintype "unspecified"))
      (node (ref "LED5") (pin "4") (pinfunction "VDD_4") (pintype "unspecified"))
      (node (ref "LED6") (pin "4") (pinfunction "VDD_4") (pintype "unspecified"))
      (node (ref "LED7") (pin "4") (pinfunction "VDD_4") (pintype "unspecified"))
      (node (ref "LED8") (pin "4") (pinfunction "VDD_4") (pintype "unspecified"))
      (node (ref "LED9") (pin "4") (pinfunction "VDD_4") (pintype "unspecified"))
      (node (ref "SW4") (pin "1") (pinfunction "1_1") (pintype "unspecified"))
      (node (ref "U1") (pin "1") (pinfunction "VIN_1") (pintype "unspecified"))
      (node (ref "U1") (pin "3") (pinfunction "CE_3") (pintype "unspecified"))
    )
    (net (code "54") (name "unconnected-(LED11-DO-Pad1)") (class "Default")
      (node (ref "LED11") (pin "1") (pinfunction "DO_1") (pintype "unspecified+no_connect"))
    )
    (net (code "55") (name "unconnected-(SW4-Pad3)") (class "Default")
      (node (ref "SW4") (pin "3") (pinfunction "3_3") (pintype "unspecified+no_connect"))
    )
    (net (code "56") (name "unconnected-(U1-NC-Pad4)") (class "Default")
      (node (ref "U1") (pin "4") (pinfunction "NC_4") (pintype "unspecified+no_connect"))
    )
    (net (code "57") (name "unconnected-(U2-IO1-Pad39)") (class "Default")
      (node (ref "U2") (pin "39") (pinfunction "IO1_39") (pintype "unspecified+no_connect"))
    )
    (net (code "58") (name "unconnected-(U2-IO2-Pad38)") (class "Default")
      (node (ref "U2") (pin "38") (pinfunction "IO2_38") (pintype "unspecified+no_connect"))
    )
    (net (code "59") (name "unconnected-(U2-IO8-Pad12)") (class "Default")
      (node (ref "U2") (pin "12") (pinfunction "IO8_12") (pintype "unspecified+no_connect"))
    )
    (net (code "60") (name "unconnected-(U2-IO13-Pad21)") (class "Default")
      (node (ref "U2") (pin "21") (pinfunction "IO13_21") (pintype "unspecified+no_connect"))
    )
    (net (code "61") (name "unconnected-(U2-IO18-Pad11)") (class "Default")
      (node (ref "U2") (pin "11") (pinfunction "IO18_11") (pintype "unspecified+no_connect"))
    )
    (net (code "62") (name "unconnected-(U2-IO35-Pad28)") (class "Default")
      (node (ref "U2") (pin "28") (pinfunction "IO35_28") (pintype "unspecified+no_connect"))
    )
    (net (code "63") (name "unconnected-(U2-IO36-Pad29)") (class "Default")
      (node (ref "U2") (pin "29") (pinfunction "IO36_29") (pintype "unspecified+no_connect"))
    )
    (net (code "64") (name "unconnected-(U2-IO37-Pad30)") (class "Default")
      (node (ref "U2") (pin "30") (pinfunction "IO37_30") (pintype "unspecified+no_connect"))
    )
    (net (code "65") (name "unconnected-(U2-IO38-Pad31)") (class "Default")
      (node (ref "U2") (pin "31") (pinfunction "IO38_31") (pintype "unspecified+no_connect"))
    )
    (net (code "66") (name "unconnected-(U2-IO39-Pad32)") (class "Default")
      (node (ref "U2") (pin "32") (pinfunction "IO39_32") (pintype "unspecified+no_connect"))
    )
    (net (code "67") (name "unconnected-(U2-IO45-Pad26)") (class "Default")
      (node (ref "U2") (pin "26") (pinfunction "IO45_26") (pintype "unspecified+no_connect"))
    )
    (net (code "68") (name "unconnected-(U2-IO48-Pad25)") (class "Default")
      (node (ref "U2") (pin "25") (pinfunction "IO48_25") (pintype "unspecified"))
    )
    (net (code "69") (name "unconnected-(U3-VBAT-Pad5)") (class "Default")
      (node (ref "U3") (pin "5") (pinfunction "VBAT_5") (pintype "unspecified+no_connect"))
    )
    (net (code "70") (name "unconnected-(U3-VBREF-Pad6)") (class "Default")
      (node (ref "U3") (pin "6") (pinfunction "VBREF_6") (pintype "unspecified+no_connect"))
    )
    (net (code "71") (name "unconnected-(USB1-SBU1-PadA8)") (class "Default")
      (node (ref "USB1") (pin "A8") (pinfunction "SBU1_A8") (pintype "unspecified+no_connect"))
    )
    (net (code "72") (name "unconnected-(USB1-SBU2-PadB8)") (class "Default")
      (node (ref "USB1") (pin "B8") (pinfunction "SBU2_B8") (pintype "unspecified+no_connect"))
    )
  )
)
